# RBFPanelV1.net
KiCad netlist of a schematic drawn in EAGLE
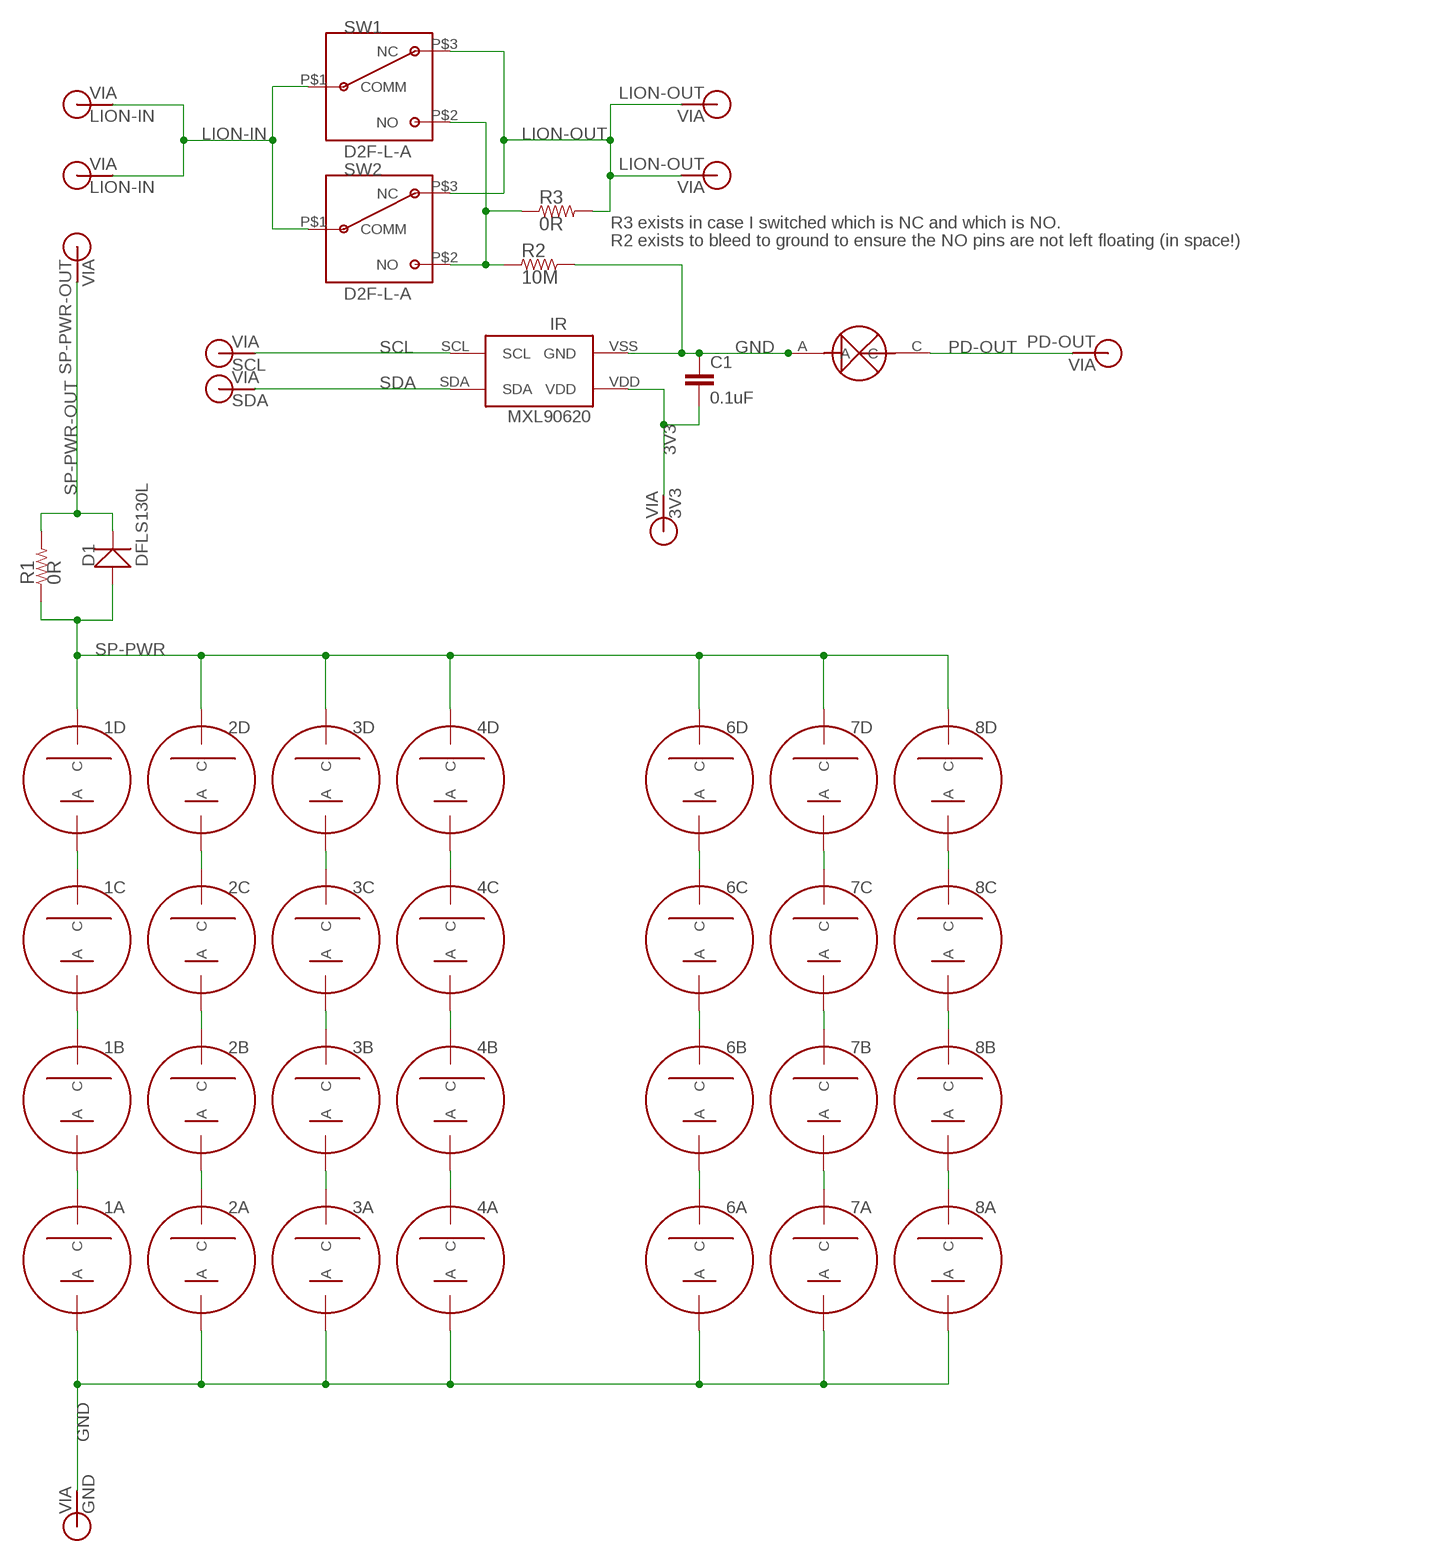
[diagram p0: schematic, sheet 1]

(export (version "E")
  (design (tool "Eeschema 10.0.6"))
  (components
    (comp (ref "1A")
      (value "SOLARCELLV3")
      (footprint "eagle-import:TRISOLX-V3")
      (libsource (lib "eagle-import") (part "SOLARCELLV3"))
    )
    (comp (ref "1B")
      (value "SOLARCELLV3")
      (footprint "eagle-import:TRISOLX-V3")
      (libsource (lib "eagle-import") (part "SOLARCELLV3"))
    )
    (comp (ref "1C")
      (value "SOLARCELLV3")
      (footprint "eagle-import:TRISOLX-V3")
      (libsource (lib "eagle-import") (part "SOLARCELLV3"))
    )
    (comp (ref "1D")
      (value "SOLARCELLV3")
      (footprint "eagle-import:TRISOLX-V3")
      (libsource (lib "eagle-import") (part "SOLARCELLV3"))
    )
    (comp (ref "2A")
      (value "SOLARCELLV3")
      (footprint "eagle-import:TRISOLX-V3")
      (libsource (lib "eagle-import") (part "SOLARCELLV3"))
    )
    (comp (ref "2B")
      (value "SOLARCELLV3")
      (footprint "eagle-import:TRISOLX-V3")
      (libsource (lib "eagle-import") (part "SOLARCELLV3"))
    )
    (comp (ref "2C")
      (value "SOLARCELLV3")
      (footprint "eagle-import:TRISOLX-V3")
      (libsource (lib "eagle-import") (part "SOLARCELLV3"))
    )
    (comp (ref "2D")
      (value "SOLARCELLV3")
      (footprint "eagle-import:TRISOLX-V3")
      (libsource (lib "eagle-import") (part "SOLARCELLV3"))
    )
    (comp (ref "3A")
      (value "SOLARCELLV3")
      (footprint "eagle-import:TRISOLX-V3")
      (libsource (lib "eagle-import") (part "SOLARCELLV3"))
    )
    (comp (ref "3B")
      (value "SOLARCELLV3")
      (footprint "eagle-import:TRISOLX-V3")
      (libsource (lib "eagle-import") (part "SOLARCELLV3"))
    )
    (comp (ref "3C")
      (value "SOLARCELLV3")
      (footprint "eagle-import:TRISOLX-V3")
      (libsource (lib "eagle-import") (part "SOLARCELLV3"))
    )
    (comp (ref "3D")
      (value "SOLARCELLV3")
      (footprint "eagle-import:TRISOLX-V3")
      (libsource (lib "eagle-import") (part "SOLARCELLV3"))
    )
    (comp (ref "3V3")
      (value "3V3")
      (footprint "eagle-import:VIA-60MIL")
      (libsource (lib "eagle-import") (part "VIA-60MIL"))
    )
    (comp (ref "4A")
      (value "SOLARCELLV3")
      (footprint "eagle-import:TRISOLX-V3")
      (libsource (lib "eagle-import") (part "SOLARCELLV3"))
    )
    (comp (ref "4B")
      (value "SOLARCELLV3")
      (footprint "eagle-import:TRISOLX-V3")
      (libsource (lib "eagle-import") (part "SOLARCELLV3"))
    )
    (comp (ref "4C")
      (value "SOLARCELLV3")
      (footprint "eagle-import:TRISOLX-V3")
      (libsource (lib "eagle-import") (part "SOLARCELLV3"))
    )
    (comp (ref "4D")
      (value "SOLARCELLV3")
      (footprint "eagle-import:TRISOLX-V3")
      (libsource (lib "eagle-import") (part "SOLARCELLV3"))
    )
    (comp (ref "6A")
      (value "SOLARCELLV3")
      (footprint "eagle-import:TRISOLX-V3")
      (libsource (lib "eagle-import") (part "SOLARCELLV3"))
    )
    (comp (ref "6B")
      (value "SOLARCELLV3")
      (footprint "eagle-import:TRISOLX-V3")
      (libsource (lib "eagle-import") (part "SOLARCELLV3"))
    )
    (comp (ref "6C")
      (value "SOLARCELLV3")
      (footprint "eagle-import:TRISOLX-V3")
      (libsource (lib "eagle-import") (part "SOLARCELLV3"))
    )
    (comp (ref "6D")
      (value "SOLARCELLV3")
      (footprint "eagle-import:TRISOLX-V3")
      (libsource (lib "eagle-import") (part "SOLARCELLV3"))
    )
    (comp (ref "7A")
      (value "SOLARCELLV3")
      (footprint "eagle-import:TRISOLX-V3")
      (libsource (lib "eagle-import") (part "SOLARCELLV3"))
    )
    (comp (ref "7B")
      (value "SOLARCELLV3")
      (footprint "eagle-import:TRISOLX-V3")
      (libsource (lib "eagle-import") (part "SOLARCELLV3"))
    )
    (comp (ref "7C")
      (value "SOLARCELLV3")
      (footprint "eagle-import:TRISOLX-V3")
      (libsource (lib "eagle-import") (part "SOLARCELLV3"))
    )
    (comp (ref "7D")
      (value "SOLARCELLV3")
      (footprint "eagle-import:TRISOLX-V3")
      (libsource (lib "eagle-import") (part "SOLARCELLV3"))
    )
    (comp (ref "8A")
      (value "SOLARCELLV3")
      (footprint "eagle-import:TRISOLX-V3")
      (libsource (lib "eagle-import") (part "SOLARCELLV3"))
    )
    (comp (ref "8B")
      (value "SOLARCELLV3")
      (footprint "eagle-import:TRISOLX-V3")
      (libsource (lib "eagle-import") (part "SOLARCELLV3"))
    )
    (comp (ref "8C")
      (value "SOLARCELLV3")
      (footprint "eagle-import:TRISOLX-V3")
      (libsource (lib "eagle-import") (part "SOLARCELLV3"))
    )
    (comp (ref "8D")
      (value "SOLARCELLV3")
      (footprint "eagle-import:TRISOLX-V3")
      (libsource (lib "eagle-import") (part "SOLARCELLV3"))
    )
    (comp (ref "C1")
      (value "0.1uF")
      (footprint "eagle-import:0805")
      (libsource (lib "eagle-import") (part "CAP0805"))
    )
    (comp (ref "D1")
      (value "DFLS130L")
      (footprint "eagle-import:PWRDI-123")
      (libsource (lib "eagle-import") (part "DFLS130L"))
    )
    (comp (ref "GND")
      (value "GND")
      (footprint "eagle-import:VIA-60MIL")
      (libsource (lib "eagle-import") (part "VIA-60MIL"))
    )
    (comp (ref "IR")
      (value "MXL90620")
      (footprint "eagle-import:MXL90620")
      (libsource (lib "eagle-import") (part "MXL90620"))
    )
    (comp (ref "PD")
      (value "PHOTODETECTOR")
      (footprint "eagle-import:PHOTODECTORDEVICE2")
      (libsource (lib "eagle-import") (part "PHOTODETECTOR"))
    )
    (comp (ref "PD-OUT")
      (value "PD-OUT")
      (footprint "eagle-import:VIA-60MIL")
      (libsource (lib "eagle-import") (part "VIA-60MIL"))
    )
    (comp (ref "PWR-OUT")
      (value "SP-PWR-OUT")
      (footprint "eagle-import:VIA-60MIL")
      (libsource (lib "eagle-import") (part "VIA-60MIL"))
    )
    (comp (ref "R1")
      (value "0R")
      (footprint "eagle-import:1210")
      (libsource (lib "eagle-import") (part "RES1210"))
    )
    (comp (ref "R2")
      (value "10M")
      (footprint "eagle-import:0805")
      (libsource (lib "eagle-import") (part "RES0805"))
    )
    (comp (ref "R3")
      (value "0R")
      (footprint "eagle-import:1210")
      (libsource (lib "eagle-import") (part "RES1210"))
    )
    (comp (ref "SCL")
      (value "SCL")
      (footprint "eagle-import:VIA-60MIL")
      (libsource (lib "eagle-import") (part "VIA-60MIL"))
    )
    (comp (ref "SDA")
      (value "SDA")
      (footprint "eagle-import:VIA-60MIL")
      (libsource (lib "eagle-import") (part "VIA-60MIL"))
    )
    (comp (ref "SW1")
      (value "D2F-L-A")
      (footprint "eagle-import:D2F-L-A")
      (libsource (lib "eagle-import") (part "D2F-L-A"))
    )
    (comp (ref "SW2")
      (value "D2F-L-A")
      (footprint "eagle-import:D2F-L-A")
      (libsource (lib "eagle-import") (part "D2F-L-A"))
    )
    (comp (ref "V1")
      (value "LION-IN")
      (footprint "eagle-import:VIA-60MIL")
      (libsource (lib "eagle-import") (part "VIA-60MIL"))
    )
    (comp (ref "V2")
      (value "LION-IN")
      (footprint "eagle-import:VIA-60MIL")
      (libsource (lib "eagle-import") (part "VIA-60MIL"))
    )
    (comp (ref "V3")
      (value "LION-OUT")
      (footprint "eagle-import:VIA-60MIL")
      (libsource (lib "eagle-import") (part "VIA-60MIL"))
    )
    (comp (ref "V4")
      (value "LION-OUT")
      (footprint "eagle-import:VIA-60MIL")
      (libsource (lib "eagle-import") (part "VIA-60MIL"))
    )
  )
  (nets
    (net (code "1") (name "/3V3") (class "Default")
      (node (ref "3V3") (pin "P$1") (pinfunction "P$1_P$1") (pintype "bidirectional"))
      (node (ref "C1") (pin "2") (pinfunction "2_2") (pintype "passive"))
      (node (ref "IR") (pin "VDD") (pinfunction "VDD_VDD") (pintype "bidirectional"))
    )
    (net (code "2") (name "/GND") (class "Default")
      (node (ref "1A") (pin "ANODE") (pinfunction "A_ANODE") (pintype "bidirectional"))
      (node (ref "2A") (pin "ANODE") (pinfunction "A_ANODE") (pintype "bidirectional"))
      (node (ref "3A") (pin "ANODE") (pinfunction "A_ANODE") (pintype "bidirectional"))
      (node (ref "4A") (pin "ANODE") (pinfunction "A_ANODE") (pintype "bidirectional"))
      (node (ref "6A") (pin "ANODE") (pinfunction "A_ANODE") (pintype "bidirectional"))
      (node (ref "7A") (pin "ANODE") (pinfunction "A_ANODE") (pintype "bidirectional"))
      (node (ref "8A") (pin "ANODE") (pinfunction "A_ANODE") (pintype "bidirectional"))
      (node (ref "C1") (pin "1") (pinfunction "1_1") (pintype "passive"))
      (node (ref "GND") (pin "P$1") (pinfunction "P$1_P$1") (pintype "bidirectional"))
      (node (ref "IR") (pin "VSS") (pinfunction "GND_VSS") (pintype "bidirectional"))
      (node (ref "PD") (pin "A") (pinfunction "A_A") (pintype "bidirectional"))
      (node (ref "R2") (pin "2") (pinfunction "2_2") (pintype "passive"))
    )
    (net (code "3") (name "/LION-IN") (class "Default")
      (node (ref "SW1") (pin "P$1") (pinfunction "COMM_P$1") (pintype "bidirectional"))
      (node (ref "SW2") (pin "P$1") (pinfunction "COMM_P$1") (pintype "bidirectional"))
      (node (ref "V1") (pin "P$1") (pinfunction "P$1_P$1") (pintype "bidirectional"))
      (node (ref "V2") (pin "P$1") (pinfunction "P$1_P$1") (pintype "bidirectional"))
    )
    (net (code "4") (name "/LION-OUT") (class "Default")
      (node (ref "R3") (pin "P$2") (pinfunction "2_P$2") (pintype "passive"))
      (node (ref "SW1") (pin "P$3") (pinfunction "NC_P$3") (pintype "bidirectional"))
      (node (ref "SW2") (pin "P$3") (pinfunction "NC_P$3") (pintype "bidirectional"))
      (node (ref "V3") (pin "P$1") (pinfunction "P$1_P$1") (pintype "bidirectional"))
      (node (ref "V4") (pin "P$1") (pinfunction "P$1_P$1") (pintype "bidirectional"))
    )
    (net (code "5") (name "/PD-OUT") (class "Default")
      (node (ref "PD") (pin "C") (pinfunction "C_C") (pintype "bidirectional"))
      (node (ref "PD-OUT") (pin "P$1") (pinfunction "P$1_P$1") (pintype "bidirectional"))
    )
    (net (code "6") (name "/SCL") (class "Default")
      (node (ref "IR") (pin "SCL") (pinfunction "SCL_SCL") (pintype "bidirectional"))
      (node (ref "SCL") (pin "P$1") (pinfunction "P$1_P$1") (pintype "bidirectional"))
    )
    (net (code "7") (name "/SDA") (class "Default")
      (node (ref "IR") (pin "SDA") (pinfunction "SDA_SDA") (pintype "bidirectional"))
      (node (ref "SDA") (pin "P$1") (pinfunction "P$1_P$1") (pintype "bidirectional"))
    )
    (net (code "8") (name "/SP-PWR") (class "Default")
      (node (ref "1D") (pin "CATHODE") (pinfunction "C_CATHODE") (pintype "bidirectional"))
      (node (ref "2D") (pin "CATHODE") (pinfunction "C_CATHODE") (pintype "bidirectional"))
      (node (ref "3D") (pin "CATHODE") (pinfunction "C_CATHODE") (pintype "bidirectional"))
      (node (ref "4D") (pin "CATHODE") (pinfunction "C_CATHODE") (pintype "bidirectional"))
      (node (ref "6D") (pin "CATHODE") (pinfunction "C_CATHODE") (pintype "bidirectional"))
      (node (ref "7D") (pin "CATHODE") (pinfunction "C_CATHODE") (pintype "bidirectional"))
      (node (ref "8D") (pin "CATHODE") (pinfunction "C_CATHODE") (pintype "bidirectional"))
      (node (ref "D1") (pin "A") (pinfunction "A_A") (pintype "bidirectional"))
      (node (ref "R1") (pin "P$1") (pinfunction "1_P$1") (pintype "passive"))
    )
    (net (code "9") (name "/SP-PWR-OUT") (class "Default")
      (node (ref "D1") (pin "C") (pinfunction "C_C") (pintype "bidirectional"))
      (node (ref "PWR-OUT") (pin "P$1") (pinfunction "P$1_P$1") (pintype "bidirectional"))
      (node (ref "R1") (pin "P$2") (pinfunction "2_P$2") (pintype "passive"))
    )
    (net (code "10") (name "Net-(1A-C)") (class "Default")
      (node (ref "1A") (pin "CATHODE") (pinfunction "C_CATHODE") (pintype "bidirectional"))
      (node (ref "1B") (pin "ANODE") (pinfunction "A_ANODE") (pintype "bidirectional"))
    )
    (net (code "11") (name "Net-(1B-C)") (class "Default")
      (node (ref "1B") (pin "CATHODE") (pinfunction "C_CATHODE") (pintype "bidirectional"))
      (node (ref "1C") (pin "ANODE") (pinfunction "A_ANODE") (pintype "bidirectional"))
    )
    (net (code "12") (name "Net-(1C-C)") (class "Default")
      (node (ref "1C") (pin "CATHODE") (pinfunction "C_CATHODE") (pintype "bidirectional"))
      (node (ref "1D") (pin "ANODE") (pinfunction "A_ANODE") (pintype "bidirectional"))
    )
    (net (code "13") (name "Net-(2A-C)") (class "Default")
      (node (ref "2A") (pin "CATHODE") (pinfunction "C_CATHODE") (pintype "bidirectional"))
      (node (ref "2B") (pin "ANODE") (pinfunction "A_ANODE") (pintype "bidirectional"))
    )
    (net (code "14") (name "Net-(2B-C)") (class "Default")
      (node (ref "2B") (pin "CATHODE") (pinfunction "C_CATHODE") (pintype "bidirectional"))
      (node (ref "2C") (pin "ANODE") (pinfunction "A_ANODE") (pintype "bidirectional"))
    )
    (net (code "15") (name "Net-(2C-C)") (class "Default")
      (node (ref "2C") (pin "CATHODE") (pinfunction "C_CATHODE") (pintype "bidirectional"))
      (node (ref "2D") (pin "ANODE") (pinfunction "A_ANODE") (pintype "bidirectional"))
    )
    (net (code "16") (name "Net-(3A-C)") (class "Default")
      (node (ref "3A") (pin "CATHODE") (pinfunction "C_CATHODE") (pintype "bidirectional"))
      (node (ref "3B") (pin "ANODE") (pinfunction "A_ANODE") (pintype "bidirectional"))
    )
    (net (code "17") (name "Net-(3B-C)") (class "Default")
      (node (ref "3B") (pin "CATHODE") (pinfunction "C_CATHODE") (pintype "bidirectional"))
      (node (ref "3C") (pin "ANODE") (pinfunction "A_ANODE") (pintype "bidirectional"))
    )
    (net (code "18") (name "Net-(3C-C)") (class "Default")
      (node (ref "3C") (pin "CATHODE") (pinfunction "C_CATHODE") (pintype "bidirectional"))
      (node (ref "3D") (pin "ANODE") (pinfunction "A_ANODE") (pintype "bidirectional"))
    )
    (net (code "19") (name "Net-(4A-C)") (class "Default")
      (node (ref "4A") (pin "CATHODE") (pinfunction "C_CATHODE") (pintype "bidirectional"))
      (node (ref "4B") (pin "ANODE") (pinfunction "A_ANODE") (pintype "bidirectional"))
    )
    (net (code "20") (name "Net-(4B-C)") (class "Default")
      (node (ref "4B") (pin "CATHODE") (pinfunction "C_CATHODE") (pintype "bidirectional"))
      (node (ref "4C") (pin "ANODE") (pinfunction "A_ANODE") (pintype "bidirectional"))
    )
    (net (code "21") (name "Net-(4C-C)") (class "Default")
      (node (ref "4C") (pin "CATHODE") (pinfunction "C_CATHODE") (pintype "bidirectional"))
      (node (ref "4D") (pin "ANODE") (pinfunction "A_ANODE") (pintype "bidirectional"))
    )
    (net (code "22") (name "Net-(6A-C)") (class "Default")
      (node (ref "6A") (pin "CATHODE") (pinfunction "C_CATHODE") (pintype "bidirectional"))
      (node (ref "6B") (pin "ANODE") (pinfunction "A_ANODE") (pintype "bidirectional"))
    )
    (net (code "23") (name "Net-(6B-C)") (class "Default")
      (node (ref "6B") (pin "CATHODE") (pinfunction "C_CATHODE") (pintype "bidirectional"))
      (node (ref "6C") (pin "ANODE") (pinfunction "A_ANODE") (pintype "bidirectional"))
    )
    (net (code "24") (name "Net-(6C-C)") (class "Default")
      (node (ref "6C") (pin "CATHODE") (pinfunction "C_CATHODE") (pintype "bidirectional"))
      (node (ref "6D") (pin "ANODE") (pinfunction "A_ANODE") (pintype "bidirectional"))
    )
    (net (code "25") (name "Net-(7A-C)") (class "Default")
      (node (ref "7A") (pin "CATHODE") (pinfunction "C_CATHODE") (pintype "bidirectional"))
      (node (ref "7B") (pin "ANODE") (pinfunction "A_ANODE") (pintype "bidirectional"))
    )
    (net (code "26") (name "Net-(7B-C)") (class "Default")
      (node (ref "7B") (pin "CATHODE") (pinfunction "C_CATHODE") (pintype "bidirectional"))
      (node (ref "7C") (pin "ANODE") (pinfunction "A_ANODE") (pintype "bidirectional"))
    )
    (net (code "27") (name "Net-(7C-C)") (class "Default")
      (node (ref "7C") (pin "CATHODE") (pinfunction "C_CATHODE") (pintype "bidirectional"))
      (node (ref "7D") (pin "ANODE") (pinfunction "A_ANODE") (pintype "bidirectional"))
    )
    (net (code "28") (name "Net-(8A-C)") (class "Default")
      (node (ref "8A") (pin "CATHODE") (pinfunction "C_CATHODE") (pintype "bidirectional"))
      (node (ref "8B") (pin "ANODE") (pinfunction "A_ANODE") (pintype "bidirectional"))
    )
    (net (code "29") (name "Net-(8B-C)") (class "Default")
      (node (ref "8B") (pin "CATHODE") (pinfunction "C_CATHODE") (pintype "bidirectional"))
      (node (ref "8C") (pin "ANODE") (pinfunction "A_ANODE") (pintype "bidirectional"))
    )
    (net (code "30") (name "Net-(8C-C)") (class "Default")
      (node (ref "8C") (pin "CATHODE") (pinfunction "C_CATHODE") (pintype "bidirectional"))
      (node (ref "8D") (pin "ANODE") (pinfunction "A_ANODE") (pintype "bidirectional"))
    )
    (net (code "31") (name "Net-(R3-1)") (class "Default")
      (node (ref "R2") (pin "1") (pinfunction "1_1") (pintype "passive"))
      (node (ref "R3") (pin "P$1") (pinfunction "1_P$1") (pintype "passive"))
      (node (ref "SW1") (pin "P$2") (pinfunction "NO_P$2") (pintype "bidirectional"))
      (node (ref "SW2") (pin "P$2") (pinfunction "NO_P$2") (pintype "bidirectional"))
    )
  )
)
